# 200_MCU.net
KiCad netlist of a schematic drawn in Altium Designer
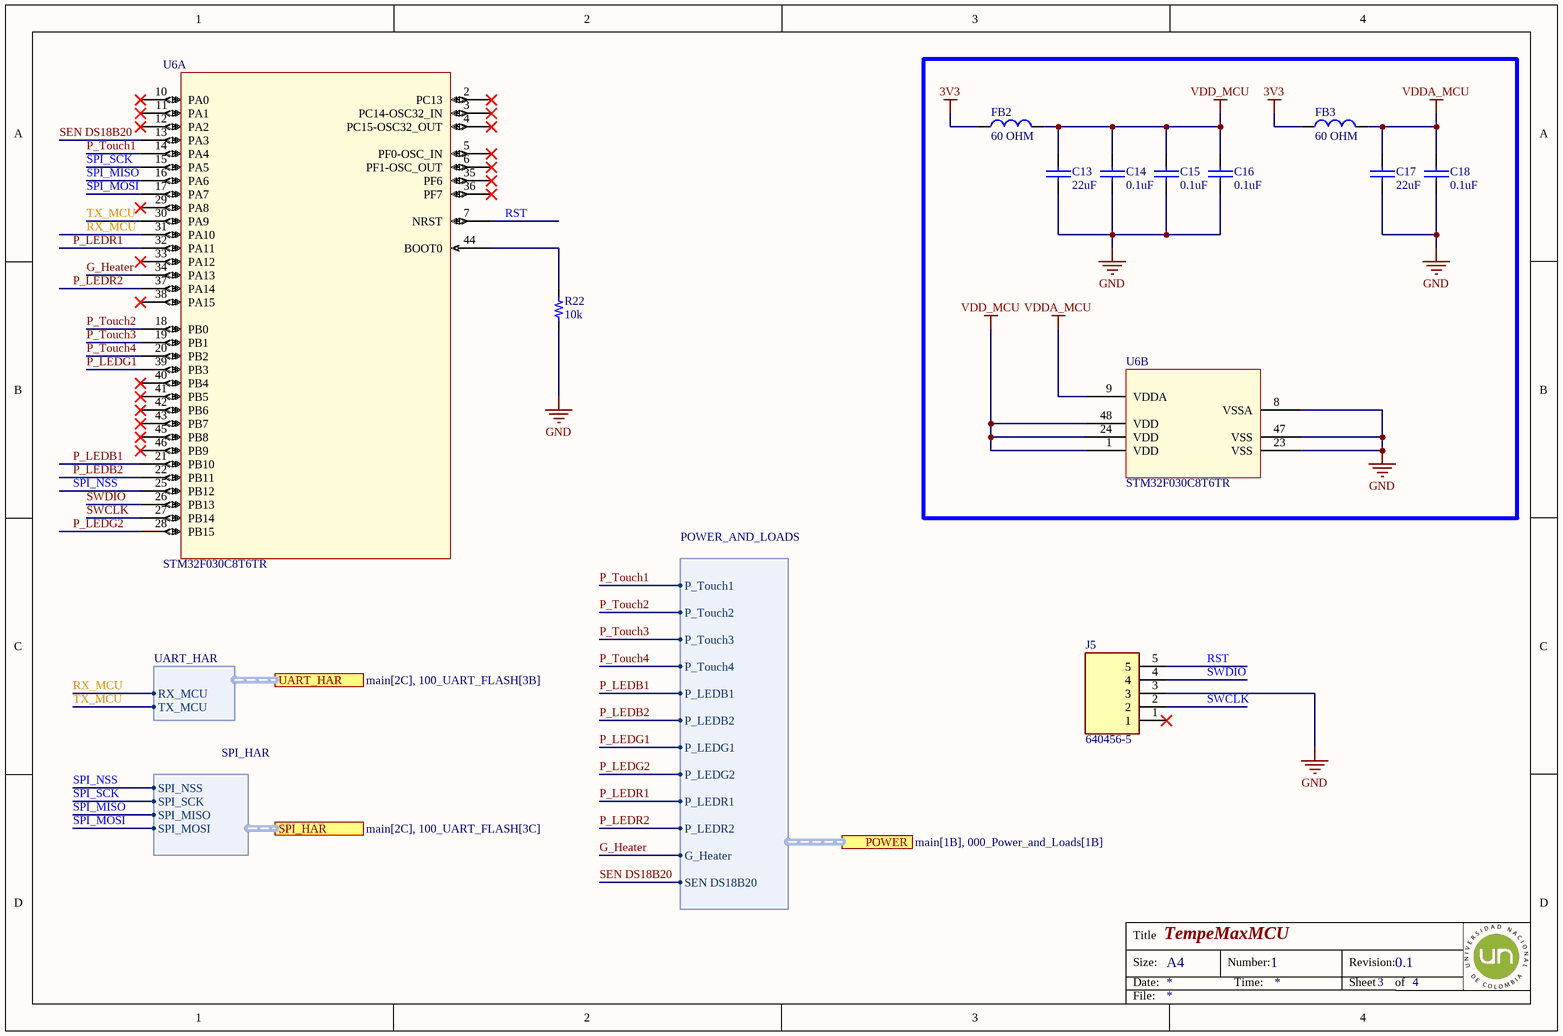
[diagram p0: 200_MCU.SchDoc]

(export (version "E")
  (design (tool "Eeschema 10.0.6"))
  (components
    (comp (ref "C13")
      (value "22uF")
      (footprint "0603_cap")
      (description "6.3V 22uF X5R ±20% 0805 Multilayer Ceramic Capacitors MLCC - SMD/SMT ROHS")
      (fields
        (field (name "MANUFACTURER") "Samsung Electro-Mechanics")
        (field (name "MANUFACTURER PART NUMBER") "CL21A226MQQNNNE")
      )
      (libsource (lib "shared_lib") (part "Cap_22uF_0805_6V3"))
    )
    (comp (ref "C14")
      (value "0.1uF")
      (footprint "0603_cap")
      (description "50V 100nF Y5V -20%~+80% 0603 Multilayer Ceramic Capacitors MLCC - SMD/SMT ROHS")
      (fields
        (field (name "MANUFACTURER") "Walsin Tech Corp")
        (field (name "MANUFACTURER PART NUMBER") "0603F104Z500CT")
      )
      (libsource (lib "shared_lib") (part "Cap_0.1uF_0603_50V"))
    )
    (comp (ref "C15")
      (value "0.1uF")
      (footprint "0603_cap")
      (description "50V 100nF Y5V -20%~+80% 0603 Multilayer Ceramic Capacitors MLCC - SMD/SMT ROHS")
      (fields
        (field (name "MANUFACTURER") "Walsin Tech Corp")
        (field (name "MANUFACTURER PART NUMBER") "0603F104Z500CT")
      )
      (libsource (lib "shared_lib") (part "Cap_0.1uF_0603_50V"))
    )
    (comp (ref "C16")
      (value "0.1uF")
      (footprint "0603_cap")
      (description "50V 100nF Y5V -20%~+80% 0603 Multilayer Ceramic Capacitors MLCC - SMD/SMT ROHS")
      (fields
        (field (name "MANUFACTURER") "Walsin Tech Corp")
        (field (name "MANUFACTURER PART NUMBER") "0603F104Z500CT")
      )
      (libsource (lib "shared_lib") (part "Cap_0.1uF_0603_50V"))
    )
    (comp (ref "C17")
      (value "22uF")
      (footprint "0603_cap")
      (description "6.3V 22uF X5R ±20% 0805 Multilayer Ceramic Capacitors MLCC - SMD/SMT ROHS")
      (fields
        (field (name "MANUFACTURER") "Samsung Electro-Mechanics")
        (field (name "MANUFACTURER PART NUMBER") "CL21A226MQQNNNE")
      )
      (libsource (lib "shared_lib") (part "Cap_22uF_0805_6V3"))
    )
    (comp (ref "C18")
      (value "0.1uF")
      (footprint "0603_cap")
      (description "50V 100nF Y5V -20%~+80% 0603 Multilayer Ceramic Capacitors MLCC - SMD/SMT ROHS")
      (fields
        (field (name "MANUFACTURER") "Walsin Tech Corp")
        (field (name "MANUFACTURER PART NUMBER") "0603F104Z500CT")
      )
      (libsource (lib "shared_lib") (part "Cap_0.1uF_0603_50V"))
    )
    (comp (ref "FB2")
      (value "60 OHM")
      (footprint "0603_fb")
      (description "2A 1 100mΩ 60Ω@100MHz ±25% 0603 Ferrite Beads ROHS")
      (fields
        (field (name "MANUFACTURER") "TAI-TECH")
        (field (name "MANUFACTURER PART NUMBER") "HCB1608KF-600T20")
      )
      (libsource (lib "shared_lib") (part "FB_60_0603_2A"))
    )
    (comp (ref "FB3")
      (value "60 OHM")
      (footprint "0603_fb")
      (description "2A 1 100mΩ 60Ω@100MHz ±25% 0603 Ferrite Beads ROHS")
      (fields
        (field (name "MANUFACTURER") "TAI-TECH")
        (field (name "MANUFACTURER PART NUMBER") "HCB1608KF-600T20")
      )
      (libsource (lib "shared_lib") (part "FB_60_0603_2A"))
    )
    (comp (ref "J5")
      (value "640456-5")
      (footprint "TE_640456-5")
      (description "Header, Friction Lock; MTA-100; 5; 250 VAC; Polyester; Tin; Copper Alloy; Tin")
      (fields (field (name "MANUFACTURER") "TE Connectivity"))
      (libsource (lib "640456-5") (part "640456-5"))
    )
    (comp (ref "R22")
      (value "10k")
      (footprint "0603_res")
      (description "RES SMD 10k OHM 5% 1/10W 0603")
      (fields (field (name "MANUFACTURER") "FOJAN") (field (name "MANUFACTURER PART NUMBER") "FRC0603J103TS"))
      (libsource (lib "shared_lib") (part "Res_10k_0603_1/10W"))
    )
    (comp (ref "U6")
      (value "STM32F030C8T6TR")
      (footprint "LQFP48_7x7mm")
      (description "IC MCU 32BIT 64KB FLASH 48LQFP")
      (fields (field (name "MANUFACTURER") "STMicroelectronics"))
      (libsource (lib "") (part "IC_STM32F030C8T6TR_LQFP48_7x7MM_1"))
    )
  )
  (nets
    (net (code "4") (name "/G_Heater") (class "Default")
      (node (ref "U6") (pin "34") (pinfunction "PA13_34") (pintype "bidirectional"))
    )
    (net (code "5") (name "/P_LEDB1") (class "Default")
      (node (ref "U6") (pin "21") (pinfunction "PB10_21") (pintype "bidirectional"))
    )
    (net (code "6") (name "/P_LEDB2") (class "Default")
      (node (ref "U6") (pin "22") (pinfunction "PB11_22") (pintype "bidirectional"))
    )
    (net (code "7") (name "/P_LEDG1") (class "Default")
      (node (ref "U6") (pin "39") (pinfunction "PB3_39") (pintype "bidirectional"))
    )
    (net (code "8") (name "/P_LEDG2") (class "Default")
      (node (ref "U6") (pin "28") (pinfunction "PB15_28") (pintype "bidirectional"))
    )
    (net (code "9") (name "/P_LEDR1") (class "Default")
      (node (ref "U6") (pin "32") (pinfunction "PA11_32") (pintype "bidirectional"))
    )
    (net (code "10") (name "/P_LEDR2") (class "Default")
      (node (ref "U6") (pin "37") (pinfunction "PA14_37") (pintype "bidirectional"))
    )
    (net (code "11") (name "/P_Touch1") (class "Default")
      (node (ref "U6") (pin "14") (pinfunction "PA4_14") (pintype "bidirectional"))
    )
    (net (code "12") (name "/P_Touch2") (class "Default")
      (node (ref "U6") (pin "18") (pinfunction "PB0_18") (pintype "bidirectional"))
    )
    (net (code "13") (name "/P_Touch3") (class "Default")
      (node (ref "U6") (pin "19") (pinfunction "PB1_19") (pintype "bidirectional"))
    )
    (net (code "14") (name "/P_Touch4") (class "Default")
      (node (ref "U6") (pin "20") (pinfunction "PB2_20") (pintype "bidirectional"))
    )
    (net (code "15") (name "/RST") (class "Default")
      (node (ref "J5") (pin "5") (pinfunction "5_5") (pintype "passive"))
      (node (ref "U6") (pin "7") (pinfunction "NRST_7") (pintype "bidirectional"))
    )
    (net (code "16") (name "/RX_MCU") (class "Default")
      (node (ref "U6") (pin "31") (pinfunction "PA10_31") (pintype "bidirectional"))
    )
    (net (code "17") (name "/SEN DS18B20") (class "Default")
      (node (ref "U6") (pin "13") (pinfunction "PA3_13") (pintype "bidirectional"))
    )
    (net (code "18") (name "/SPI_MISO") (class "Default")
      (node (ref "U6") (pin "16") (pinfunction "PA6_16") (pintype "bidirectional"))
    )
    (net (code "19") (name "/SPI_MOSI") (class "Default")
      (node (ref "U6") (pin "17") (pinfunction "PA7_17") (pintype "bidirectional"))
    )
    (net (code "20") (name "/SPI_NSS") (class "Default")
      (node (ref "U6") (pin "25") (pinfunction "PB12_25") (pintype "bidirectional"))
    )
    (net (code "21") (name "/SPI_SCK") (class "Default")
      (node (ref "U6") (pin "15") (pinfunction "PA5_15") (pintype "bidirectional"))
    )
    (net (code "22") (name "/SWCLK") (class "Default")
      (node (ref "J5") (pin "2") (pinfunction "2_2") (pintype "passive"))
      (node (ref "U6") (pin "27") (pinfunction "PB14_27") (pintype "bidirectional"))
    )
    (net (code "23") (name "/SWDIO") (class "Default")
      (node (ref "J5") (pin "4") (pinfunction "4_4") (pintype "passive"))
      (node (ref "U6") (pin "26") (pinfunction "PB13_26") (pintype "bidirectional"))
    )
    (net (code "24") (name "/TX_MCU") (class "Default")
      (node (ref "U6") (pin "30") (pinfunction "PA9_30") (pintype "bidirectional"))
    )
    (net (code "28") (name "3V3") (class "Default")
      (node (ref "FB2") (pin "1") (pinfunction "1_1") (pintype "passive"))
      (node (ref "FB3") (pin "1") (pinfunction "1_1") (pintype "passive"))
    )
    (net (code "29") (name "GND") (class "Default")
      (node (ref "C13") (pin "2") (pinfunction "2_2") (pintype "passive"))
      (node (ref "C14") (pin "2") (pinfunction "2_2") (pintype "passive"))
      (node (ref "C15") (pin "2") (pinfunction "2_2") (pintype "passive"))
      (node (ref "C16") (pin "2") (pinfunction "2_2") (pintype "passive"))
      (node (ref "C17") (pin "2") (pinfunction "2_2") (pintype "passive"))
      (node (ref "C18") (pin "2") (pinfunction "2_2") (pintype "passive"))
      (node (ref "J5") (pin "3") (pinfunction "3_3") (pintype "passive"))
      (node (ref "R22") (pin "1") (pinfunction "1_1") (pintype "passive"))
      (node (ref "U6") (pin "23") (pinfunction "VSS_23") (pintype "power_in"))
      (node (ref "U6") (pin "47") (pinfunction "VSS_47") (pintype "power_in"))
      (node (ref "U6") (pin "8") (pinfunction "VSSA_8") (pintype "power_in"))
    )
    (net (code "30") (name "Net-(U6A-BOOT0)") (class "Default")
      (node (ref "R22") (pin "2") (pinfunction "2_2") (pintype "passive"))
      (node (ref "U6") (pin "44") (pinfunction "BOOT0_44") (pintype "input"))
    )
    (net (code "31") (name "VDDA_MCU") (class "Default")
      (node (ref "C17") (pin "1") (pinfunction "1_1") (pintype "passive"))
      (node (ref "C18") (pin "1") (pinfunction "1_1") (pintype "passive"))
      (node (ref "FB3") (pin "2") (pinfunction "2_2") (pintype "passive"))
      (node (ref "U6") (pin "9") (pinfunction "VDDA_9") (pintype "power_in"))
    )
    (net (code "32") (name "VDD_MCU") (class "Default")
      (node (ref "C13") (pin "1") (pinfunction "1_1") (pintype "passive"))
      (node (ref "C14") (pin "1") (pinfunction "1_1") (pintype "passive"))
      (node (ref "C15") (pin "1") (pinfunction "1_1") (pintype "passive"))
      (node (ref "C16") (pin "1") (pinfunction "1_1") (pintype "passive"))
      (node (ref "FB2") (pin "2") (pinfunction "2_2") (pintype "passive"))
      (node (ref "U6") (pin "1") (pinfunction "VDD_1") (pintype "power_in"))
      (node (ref "U6") (pin "24") (pinfunction "VDD_24") (pintype "power_in"))
      (node (ref "U6") (pin "48") (pinfunction "VDD_48") (pintype "power_in"))
    )
    (net (code "33") (name "unconnected-(J5-Pad1)") (class "Default")
      (node (ref "J5") (pin "1") (pinfunction "1_1") (pintype "passive+no_connect"))
    )
    (net (code "34") (name "unconnected-(U6A-PA0-Pad10)") (class "Default")
      (node (ref "U6") (pin "10") (pinfunction "PA0_10") (pintype "bidirectional+no_connect"))
    )
    (net (code "35") (name "unconnected-(U6A-PA1-Pad11)") (class "Default")
      (node (ref "U6") (pin "11") (pinfunction "PA1_11") (pintype "bidirectional+no_connect"))
    )
    (net (code "36") (name "unconnected-(U6A-PA2-Pad12)") (class "Default")
      (node (ref "U6") (pin "12") (pinfunction "PA2_12") (pintype "bidirectional+no_connect"))
    )
    (net (code "37") (name "unconnected-(U6A-PA8-Pad29)") (class "Default")
      (node (ref "U6") (pin "29") (pinfunction "PA8_29") (pintype "bidirectional+no_connect"))
    )
    (net (code "38") (name "unconnected-(U6A-PA12-Pad33)") (class "Default")
      (node (ref "U6") (pin "33") (pinfunction "PA12_33") (pintype "bidirectional+no_connect"))
    )
    (net (code "39") (name "unconnected-(U6A-PA15-Pad38)") (class "Default")
      (node (ref "U6") (pin "38") (pinfunction "PA15_38") (pintype "bidirectional+no_connect"))
    )
    (net (code "40") (name "unconnected-(U6A-PB4-Pad40)") (class "Default")
      (node (ref "U6") (pin "40") (pinfunction "PB4_40") (pintype "bidirectional+no_connect"))
    )
    (net (code "41") (name "unconnected-(U6A-PB5-Pad41)") (class "Default")
      (node (ref "U6") (pin "41") (pinfunction "PB5_41") (pintype "bidirectional+no_connect"))
    )
    (net (code "42") (name "unconnected-(U6A-PB6-Pad42)") (class "Default")
      (node (ref "U6") (pin "42") (pinfunction "PB6_42") (pintype "bidirectional+no_connect"))
    )
    (net (code "43") (name "unconnected-(U6A-PB7-Pad43)") (class "Default")
      (node (ref "U6") (pin "43") (pinfunction "PB7_43") (pintype "bidirectional+no_connect"))
    )
    (net (code "44") (name "unconnected-(U6A-PB8-Pad45)") (class "Default")
      (node (ref "U6") (pin "45") (pinfunction "PB8_45") (pintype "bidirectional+no_connect"))
    )
    (net (code "45") (name "unconnected-(U6A-PB9-Pad46)") (class "Default")
      (node (ref "U6") (pin "46") (pinfunction "PB9_46") (pintype "bidirectional+no_connect"))
    )
    (net (code "46") (name "unconnected-(U6A-PC13-Pad2)") (class "Default")
      (node (ref "U6") (pin "2") (pinfunction "PC13_2") (pintype "bidirectional+no_connect"))
    )
    (net (code "47") (name "unconnected-(U6A-PC14-OSC32_IN-Pad3)") (class "Default")
      (node (ref "U6") (pin "3") (pinfunction "PC14-OSC32_IN_3") (pintype "bidirectional+no_connect"))
    )
    (net (code "48") (name "unconnected-(U6A-PC15-OSC32_OUT-Pad4)") (class "Default")
      (node (ref "U6") (pin "4") (pinfunction "PC15-OSC32_OUT_4") (pintype "bidirectional+no_connect"))
    )
    (net (code "49") (name "unconnected-(U6A-PF0-OSC_IN-Pad5)") (class "Default")
      (node (ref "U6") (pin "5") (pinfunction "PF0-OSC_IN_5") (pintype "bidirectional+no_connect"))
    )
    (net (code "50") (name "unconnected-(U6A-PF1-OSC_OUT-Pad6)") (class "Default")
      (node (ref "U6") (pin "6") (pinfunction "PF1-OSC_OUT_6") (pintype "bidirectional+no_connect"))
    )
    (net (code "51") (name "unconnected-(U6A-PF6-Pad35)") (class "Default")
      (node (ref "U6") (pin "35") (pinfunction "PF6_35") (pintype "bidirectional+no_connect"))
    )
    (net (code "52") (name "unconnected-(U6A-PF7-Pad36)") (class "Default")
      (node (ref "U6") (pin "36") (pinfunction "PF7_36") (pintype "bidirectional+no_connect"))
    )
  )
)
